# OptocouplerV2.net
KiCad netlist of a schematic drawn in Altium Designer
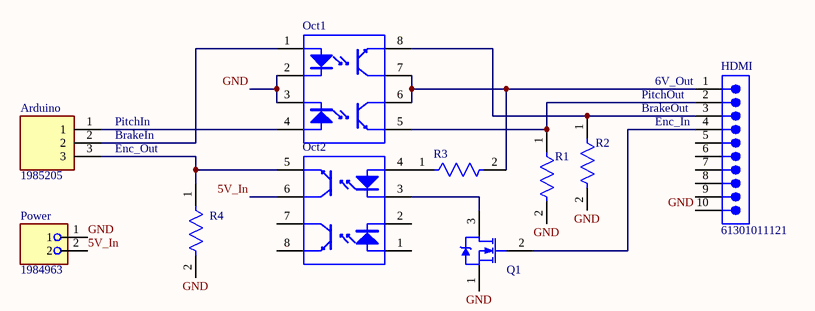
[diagram p0: OptocouplerV2.SchDoc]

(export (version "E")
  (design (tool "Eeschema 10.0.6"))
  (components
    (comp (ref "Arduino")
      (value "1985205")
      (footprint "TE_1985205")
      (description "PCB Terminal Push-In 3.5mm 16AWG 400V 8A 3 Position COMBICON PTSA Series")
      (fields (field (name "MF") "Phoenix Contact"))
      (libsource (lib "Capstone") (part "1985205"))
    )
    (comp (ref "HDMI")
      (value "61301011121")
      (footprint "61301011121")
      (libsource (lib "Altium Content Vault") (part "Header_Male_1R_10P"))
    )
    (comp (ref "Oct1")
      (value "~")
      (footprint "VISH-DIP8")
      (description "Optocoupler, Phototransistor Output, Dual Channel, 1.3 V, -55 to 100 degC, 8-Pin DIP, RoHS, Tube")
      (fields (field (name "TOLERANCE") "1%"))
      (libsource (lib "Altium Content Vault") (part "OPTO-AKKAECCE-8"))
    )
    (comp (ref "Oct2")
      (value "~")
      (footprint "VISH-DIP8")
      (description "Optocoupler, Phototransistor Output, Dual Channel, 1.3 V, -55 to 100 degC, 8-Pin DIP, RoHS, Tube")
      (fields (field (name "TOLERANCE") "1%"))
      (libsource (lib "Altium Content Vault") (part "OPTO-AKKAECCE-8"))
    )
    (comp (ref "Power")
      (value "1984963")
      (footprint "PHOENIX_1984963")
      (libsource (lib "Capstone") (part "1984963"))
    )
    (comp (ref "Q1")
      (value "~")
      (footprint "ONSC-TO-92-3-29-11_AM_BL")
      (description "Small Signal MOSFET, 200 mA, 60 V, N-Channel, 3-Pin TO-92, Pb-Free, Tape and Reel")
      (fields (field (name "MANUFACTURER") "On Semiconductor") (field (name "PARTNUMBER") "2N7000RLRAG"))
      (libsource (lib "Altium Content Vault") (part "ONSC-NMOS-S1G2D3-3"))
    )
    (comp (ref "R1")
      (value "~")
      (footprint "FP-MRS25-MFG")
      (fields (field (name "TOLERANCE") "1%"))
      (libsource (lib "Altium Content Vault") (part "1029c3af85768c4190bb7ad29bc67b5"))
    )
    (comp (ref "R2")
      (value "~")
      (footprint "FP-MRS25-MFG")
      (fields (field (name "TOLERANCE") "1%"))
      (libsource (lib "Altium Content Vault") (part "1029c3af85768c4190bb7ad29bc67b5"))
    )
    (comp (ref "R3")
      (value "~")
      (footprint "FP-MRS25-MFG")
      (fields (field (name "TOLERANCE") "1%"))
      (libsource (lib "Altium Content Vault") (part "1029c3af85768c4190bb7ad29bc67b5"))
    )
    (comp (ref "R4")
      (value "~")
      (footprint "FP-MRS25-MFG")
      (fields (field (name "TOLERANCE") "1%"))
      (libsource (lib "Altium Content Vault") (part "1029c3af85768c4190bb7ad29bc67b5"))
    )
  )
  (nets
    (net (code "1") (name "/5V_In") (class "Default")
      (node (ref "Oct2") (pin "6") (pinfunction "C_6") (pintype "passive"))
      (node (ref "Power") (pin "2") (pinfunction "2_2") (pintype "passive"))
    )
    (net (code "2") (name "/GND") (class "Default")
      (node (ref "HDMI") (pin "10") (pinfunction "10_10") (pintype "passive"))
      (node (ref "Oct1") (pin "2") (pinfunction "C_2") (pintype "passive"))
      (node (ref "Oct1") (pin "3") (pinfunction "C_3") (pintype "passive"))
      (node (ref "Power") (pin "1") (pinfunction "1_1") (pintype "passive"))
      (node (ref "Q1") (pin "1") (pinfunction "S_1") (pintype "passive"))
      (node (ref "R1") (pin "2") (pinfunction "2_2") (pintype "passive"))
      (node (ref "R2") (pin "2") (pinfunction "2_2") (pintype "passive"))
      (node (ref "R4") (pin "2") (pinfunction "2_2") (pintype "passive"))
    )
    (net (code "3") (name "Net-(Arduino-Pad1)") (class "Default")
      (node (ref "Arduino") (pin "1") (pinfunction "1_1") (pintype "passive"))
      (node (ref "Oct1") (pin "4") (pinfunction "A_4") (pintype "passive"))
    )
    (net (code "4") (name "Net-(Arduino-Pad2)") (class "Default")
      (node (ref "Arduino") (pin "2") (pinfunction "2_2") (pintype "passive"))
      (node (ref "Oct1") (pin "1") (pinfunction "A_1") (pintype "passive"))
    )
    (net (code "5") (name "Net-(Arduino-Pad3)") (class "Default")
      (node (ref "Arduino") (pin "3") (pinfunction "3_3") (pintype "passive"))
      (node (ref "Oct2") (pin "5") (pinfunction "E_5") (pintype "passive"))
      (node (ref "R4") (pin "1") (pinfunction "1_1") (pintype "passive"))
    )
    (net (code "6") (name "Net-(HDMI-Pad1)") (class "Default")
      (node (ref "HDMI") (pin "1") (pinfunction "1_1") (pintype "passive"))
      (node (ref "Oct1") (pin "6") (pinfunction "C_6") (pintype "passive"))
      (node (ref "Oct1") (pin "7") (pinfunction "C_7") (pintype "passive"))
      (node (ref "R3") (pin "2") (pinfunction "2_2") (pintype "passive"))
    )
    (net (code "7") (name "Net-(HDMI-Pad2)") (class "Default")
      (node (ref "HDMI") (pin "2") (pinfunction "2_2") (pintype "passive"))
      (node (ref "Oct1") (pin "5") (pinfunction "E_5") (pintype "passive"))
      (node (ref "R1") (pin "1") (pinfunction "1_1") (pintype "passive"))
    )
    (net (code "8") (name "Net-(HDMI-Pad3)") (class "Default")
      (node (ref "HDMI") (pin "3") (pinfunction "3_3") (pintype "passive"))
      (node (ref "Oct1") (pin "8") (pinfunction "E_8") (pintype "passive"))
      (node (ref "R2") (pin "1") (pinfunction "1_1") (pintype "passive"))
    )
    (net (code "9") (name "Net-(Oct2-A-Pad4)") (class "Default")
      (node (ref "Oct2") (pin "4") (pinfunction "A_4") (pintype "passive"))
      (node (ref "R3") (pin "1") (pinfunction "1_1") (pintype "passive"))
    )
    (net (code "10") (name "Net-(Q1-D)") (class "Default")
      (node (ref "Oct2") (pin "3") (pinfunction "C_3") (pintype "passive"))
      (node (ref "Q1") (pin "3") (pinfunction "D_3") (pintype "passive"))
    )
    (net (code "11") (name "Net-(Q1-G)") (class "Default")
      (node (ref "HDMI") (pin "4") (pinfunction "4_4") (pintype "passive"))
      (node (ref "Q1") (pin "2") (pinfunction "G_2") (pintype "passive"))
    )
    (net (code "12") (name "unconnected-(HDMI-Pad5)") (class "Default")
      (node (ref "HDMI") (pin "5") (pinfunction "5_5") (pintype "passive"))
    )
    (net (code "13") (name "unconnected-(HDMI-Pad6)") (class "Default")
      (node (ref "HDMI") (pin "6") (pinfunction "6_6") (pintype "passive"))
    )
    (net (code "14") (name "unconnected-(HDMI-Pad7)") (class "Default")
      (node (ref "HDMI") (pin "7") (pinfunction "7_7") (pintype "passive"))
    )
    (net (code "15") (name "unconnected-(HDMI-Pad8)") (class "Default")
      (node (ref "HDMI") (pin "8") (pinfunction "8_8") (pintype "passive"))
    )
    (net (code "16") (name "unconnected-(HDMI-Pad9)") (class "Default")
      (node (ref "HDMI") (pin "9") (pinfunction "9_9") (pintype "passive"))
    )
    (net (code "17") (name "unconnected-(Oct2-A-Pad1)") (class "Default")
      (node (ref "Oct2") (pin "1") (pinfunction "A_1") (pintype "passive"))
    )
    (net (code "18") (name "unconnected-(Oct2-C-Pad2)") (class "Default")
      (node (ref "Oct2") (pin "2") (pinfunction "C_2") (pintype "passive"))
    )
    (net (code "19") (name "unconnected-(Oct2-C-Pad7)") (class "Default")
      (node (ref "Oct2") (pin "7") (pinfunction "C_7") (pintype "passive"))
    )
    (net (code "20") (name "unconnected-(Oct2-E-Pad8)") (class "Default")
      (node (ref "Oct2") (pin "8") (pinfunction "E_8") (pintype "passive"))
    )
  )
)
